# source.net
KiCad netlist of a schematic drawn in Altium Designer
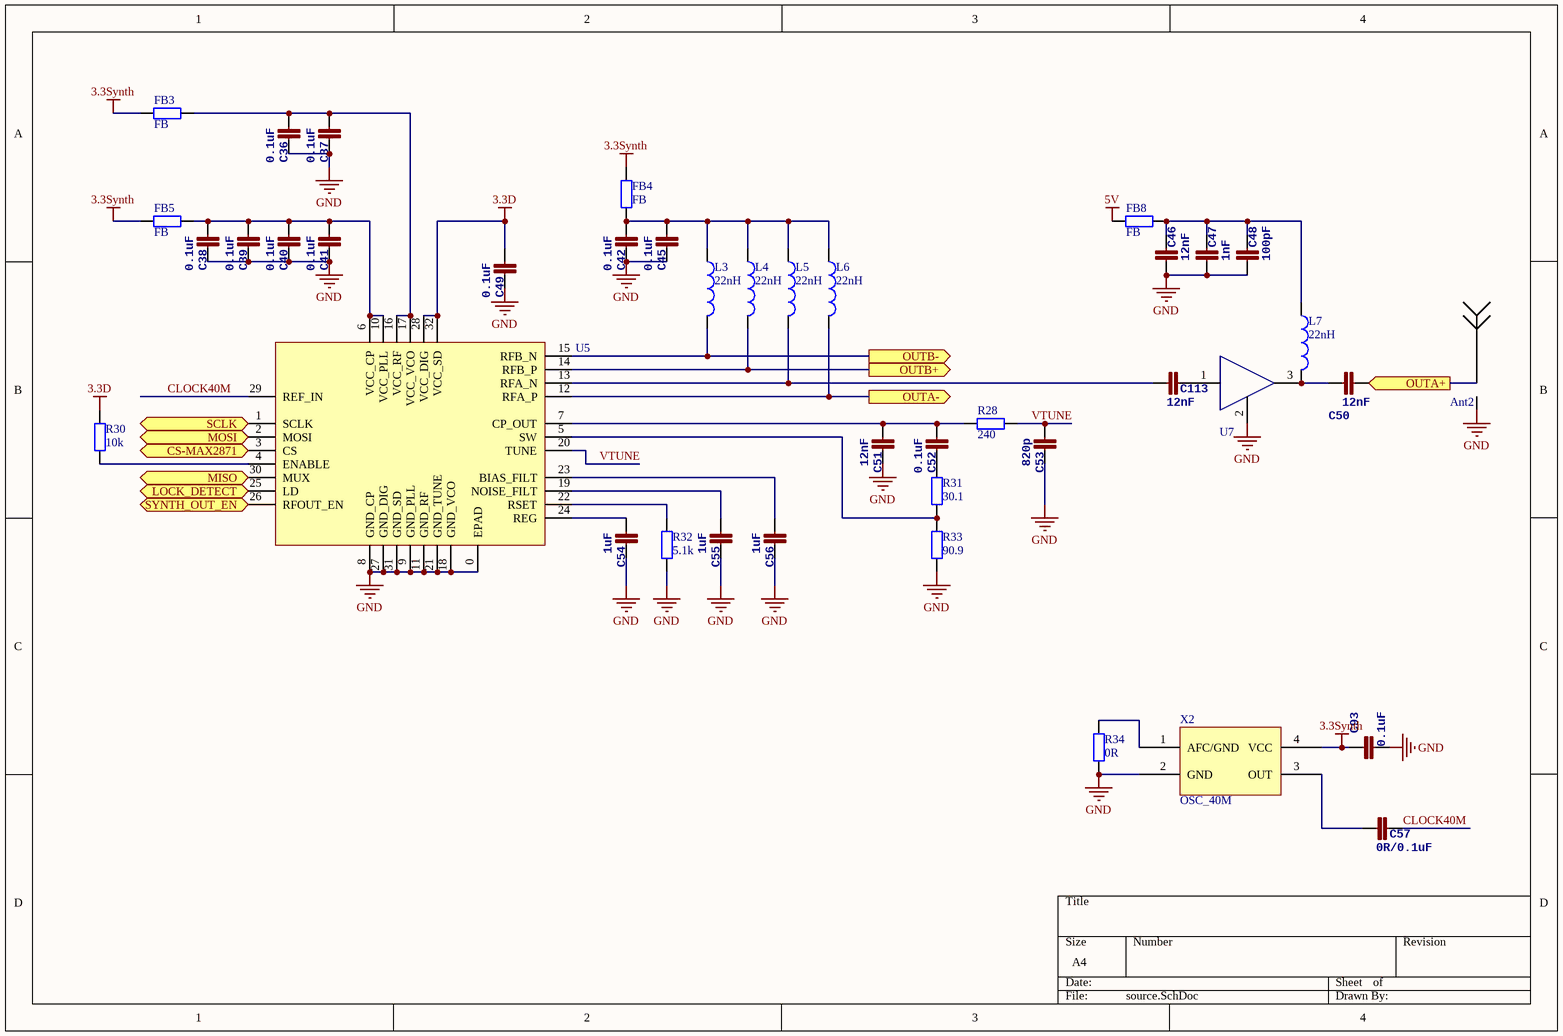
[diagram p0: source.SchDoc]

(export (version "E")
  (design (tool "Eeschema 10.0.6"))
  (components
    (comp (ref "Ant2") (value "Antenna") (footprint "SMA-2") (libsource (lib "F4SDR") (part "Antenna")))
    (comp (ref "C36")
      (value "0.1uF")
      (footprint "0402")
      (description "<b>Capacitor</b>\nStandard 0603 ceramic capacitor, and 0.1\" leaded capacitor.")
      (fields (field (name "PARTNO") "CC0402ZRY5V7BB104"))
      (libsource (lib "pixhawk2") (part "CAP0402-CAP"))
    )
    (comp (ref "C37")
      (value "0.1uF")
      (footprint "0402")
      (description "<b>Capacitor</b>\nStandard 0603 ceramic capacitor, and 0.1\" leaded capacitor.")
      (fields (field (name "PARTNO") "CC0402ZRY5V7BB104"))
      (libsource (lib "pixhawk2") (part "CAP0402-CAP"))
    )
    (comp (ref "C38")
      (value "0.1uF")
      (footprint "0402")
      (description "<b>Capacitor</b>\nStandard 0603 ceramic capacitor, and 0.1\" leaded capacitor.")
      (fields (field (name "PARTNO") "CC0402ZRY5V7BB104"))
      (libsource (lib "pixhawk2") (part "CAP0402-CAP"))
    )
    (comp (ref "C39")
      (value "0.1uF")
      (footprint "0402")
      (description "<b>Capacitor</b>\nStandard 0603 ceramic capacitor, and 0.1\" leaded capacitor.")
      (fields (field (name "PARTNO") "CC0402ZRY5V7BB104"))
      (libsource (lib "pixhawk2") (part "CAP0402-CAP"))
    )
    (comp (ref "C40")
      (value "0.1uF")
      (footprint "0402")
      (description "<b>Capacitor</b>\nStandard 0603 ceramic capacitor, and 0.1\" leaded capacitor.")
      (fields (field (name "PARTNO") "CC0402ZRY5V7BB104"))
      (libsource (lib "pixhawk2") (part "CAP0402-CAP"))
    )
    (comp (ref "C41")
      (value "0.1uF")
      (footprint "0402")
      (description "<b>Capacitor</b>\nStandard 0603 ceramic capacitor, and 0.1\" leaded capacitor.")
      (fields (field (name "PARTNO") "CC0402ZRY5V7BB104"))
      (libsource (lib "pixhawk2") (part "CAP0402-CAP"))
    )
    (comp (ref "C42")
      (value "0.1uF")
      (footprint "0402")
      (description "<b>Capacitor</b>\nStandard 0603 ceramic capacitor, and 0.1\" leaded capacitor.")
      (fields (field (name "PARTNO") "CC0402ZRY5V7BB104"))
      (libsource (lib "pixhawk2") (part "CAP0402-CAP"))
    )
    (comp (ref "C45")
      (value "0.1uF")
      (footprint "0402")
      (description "<b>Capacitor</b>\nStandard 0603 ceramic capacitor, and 0.1\" leaded capacitor.")
      (fields (field (name "PARTNO") "CC0402ZRY5V7BB104"))
      (libsource (lib "pixhawk2") (part "CAP0402-CAP"))
    )
    (comp (ref "C46")
      (value "12nF")
      (footprint "0805")
      (description "<b>Capacitor</b>\nStandard 0603 ceramic capacitor, and 0.1\" leaded capacitor.")
      (fields (field (name "PARTNO") "CC0402ZRY5V7BB104"))
      (libsource (lib "") (part "CAP0402-CAP_2"))
    )
    (comp (ref "C47")
      (value "1nF")
      (footprint "0402")
      (description "<b>Capacitor</b>\nStandard 0603 ceramic capacitor, and 0.1\" leaded capacitor.")
      (fields (field (name "PARTNO") "CC0402ZRY5V7BB104"))
      (libsource (lib "") (part "CAP0402-CAP_2"))
    )
    (comp (ref "C48")
      (value "100pF")
      (footprint "0402")
      (description "<b>Capacitor</b>\nStandard 0603 ceramic capacitor, and 0.1\" leaded capacitor.")
      (fields (field (name "PARTNO") "CC0402ZRY5V7BB104"))
      (libsource (lib "") (part "CAP0402-CAP_2"))
    )
    (comp (ref "C49")
      (value "0.1uF")
      (footprint "0402")
      (description "<b>Capacitor</b>\nStandard 0603 ceramic capacitor, and 0.1\" leaded capacitor.")
      (fields (field (name "PARTNO") "CC0402ZRY5V7BB104"))
      (libsource (lib "pixhawk2") (part "CAP0402-CAP"))
    )
    (comp (ref "C50")
      (value "12nF")
      (footprint "0402")
      (description "<b>Capacitor</b>\nStandard 0603 ceramic capacitor, and 0.1\" leaded capacitor.")
      (fields (field (name "PARTNO") "CC0402ZRY5V7BB104"))
      (libsource (lib "") (part "CAP0402-CAP_1"))
    )
    (comp (ref "C51")
      (value "12nF")
      (footprint "0402")
      (description "<b>Capacitor</b>\nStandard 0603 ceramic capacitor, and 0.1\" leaded capacitor.")
      (fields (field (name "PARTNO") "CC0402ZRY5V7BB104"))
      (libsource (lib "pixhawk2") (part "CAP0402-CAP"))
    )
    (comp (ref "C52")
      (value "0.1uF")
      (footprint "0402")
      (description "<b>Capacitor</b>\nStandard 0603 ceramic capacitor, and 0.1\" leaded capacitor.")
      (fields (field (name "PARTNO") "CC0402ZRY5V7BB104"))
      (libsource (lib "pixhawk2") (part "CAP0402-CAP"))
    )
    (comp (ref "C53")
      (value "820p")
      (footprint "0402")
      (description "<b>Capacitor</b>\nStandard 0603 ceramic capacitor, and 0.1\" leaded capacitor.")
      (fields (field (name "PARTNO") "CC0402ZRY5V7BB104"))
      (libsource (lib "pixhawk2") (part "CAP0402-CAP"))
    )
    (comp (ref "C54")
      (value "1uF")
      (footprint "0402")
      (description "<b>Capacitor</b>\nStandard 0603 ceramic capacitor, and 0.1\" leaded capacitor.")
      (fields (field (name "PARTNO") "CC0402ZRY5V7BB104"))
      (libsource (lib "pixhawk2") (part "CAP0402-CAP"))
    )
    (comp (ref "C55")
      (value "1uF")
      (footprint "0402")
      (description "<b>Capacitor</b>\nStandard 0603 ceramic capacitor, and 0.1\" leaded capacitor.")
      (fields (field (name "PARTNO") "CC0402ZRY5V7BB104"))
      (libsource (lib "pixhawk2") (part "CAP0402-CAP"))
    )
    (comp (ref "C56")
      (value "1uF")
      (footprint "0402")
      (description "<b>Capacitor</b>\nStandard 0603 ceramic capacitor, and 0.1\" leaded capacitor.")
      (fields (field (name "PARTNO") "CC0402ZRY5V7BB104"))
      (libsource (lib "pixhawk2") (part "CAP0402-CAP"))
    )
    (comp (ref "C57")
      (value "0R/0.1uF")
      (footprint "0402")
      (description "<b>Capacitor</b>\nStandard 0603 ceramic capacitor, and 0.1\" leaded capacitor.")
      (fields (field (name "PARTNO") "CC0402ZRY5V7BB104"))
      (libsource (lib "") (part "CAP0402-CAP_1"))
    )
    (comp (ref "C93")
      (value "0.1uF")
      (footprint "0402")
      (description "<b>Capacitor</b>\nStandard 0603 ceramic capacitor, and 0.1\" leaded capacitor.")
      (fields (field (name "PARTNO") "CC0402ZRY5V7BB104"))
      (libsource (lib "") (part "CAP0402-CAP_1"))
    )
    (comp (ref "C113")
      (value "12nF")
      (footprint "0402")
      (description "<b>Capacitor</b>\nStandard 0603 ceramic capacitor, and 0.1\" leaded capacitor.")
      (fields (field (name "PARTNO") "CC0402ZRY5V7BB104"))
      (libsource (lib "") (part "CAP0402-CAP_1"))
    )
    (comp (ref "FB3")
      (value "FB")
      (footprint "0603")
      (description "Resistor")
      (fields (field (name "PUBLISHER") "Altium Limited"))
      (libsource (lib "") (part "Res2_2"))
    )
    (comp (ref "FB4")
      (value "FB")
      (footprint "0603")
      (description "Resistor")
      (fields (field (name "PUBLISHER") "Altium Limited"))
      (libsource (lib "") (part "Res2_3"))
    )
    (comp (ref "FB5")
      (value "FB")
      (footprint "0603")
      (description "Resistor")
      (fields (field (name "PUBLISHER") "Altium Limited"))
      (libsource (lib "") (part "Res2_2"))
    )
    (comp (ref "FB8")
      (value "FB")
      (footprint "0603")
      (description "Resistor")
      (fields (field (name "PUBLISHER") "Altium Limited"))
      (libsource (lib "") (part "Res2_1"))
    )
    (comp (ref "L3")
      (value "22nH")
      (footprint "0402")
      (description "Inductor")
      (fields (field (name "PUBLISHER") "Altium Limited"))
      (libsource (lib "Miscellaneous Devices") (part "Inductor"))
    )
    (comp (ref "L4")
      (value "22nH")
      (footprint "0402")
      (description "Inductor")
      (fields (field (name "PUBLISHER") "Altium Limited"))
      (libsource (lib "Miscellaneous Devices") (part "Inductor"))
    )
    (comp (ref "L5")
      (value "22nH")
      (footprint "0402")
      (description "Inductor")
      (fields (field (name "PUBLISHER") "Altium Limited"))
      (libsource (lib "Miscellaneous Devices") (part "Inductor"))
    )
    (comp (ref "L6")
      (value "22nH")
      (footprint "0402")
      (description "Inductor")
      (fields (field (name "PUBLISHER") "Altium Limited"))
      (libsource (lib "Miscellaneous Devices") (part "Inductor"))
    )
    (comp (ref "L7")
      (value "22nH")
      (footprint "0603")
      (description "Inductor")
      (fields (field (name "PUBLISHER") "Altium Limited"))
      (libsource (lib "Miscellaneous Devices") (part "Inductor"))
    )
    (comp (ref "R28")
      (value "240")
      (footprint "0402")
      (description "Resistor")
      (fields (field (name "PUBLISHER") "Altium Limited"))
      (libsource (lib "") (part "Res2_2"))
    )
    (comp (ref "R30")
      (value "10k")
      (footprint "0402")
      (description "Resistor")
      (fields (field (name "PUBLISHER") "Altium Limited"))
      (libsource (lib "Miscellaneous Devices") (part "Res2"))
    )
    (comp (ref "R31")
      (value "30.1")
      (footprint "0402")
      (description "Resistor")
      (fields (field (name "PUBLISHER") "Altium Limited"))
      (libsource (lib "Miscellaneous Devices") (part "Res2"))
    )
    (comp (ref "R32")
      (value "5.1k")
      (footprint "0402")
      (description "Resistor")
      (fields (field (name "PUBLISHER") "Altium Limited"))
      (libsource (lib "Miscellaneous Devices") (part "Res2"))
    )
    (comp (ref "R33")
      (value "90.9")
      (footprint "0402")
      (description "Resistor")
      (fields (field (name "PUBLISHER") "Altium Limited"))
      (libsource (lib "Miscellaneous Devices") (part "Res2"))
    )
    (comp (ref "R34")
      (value "0R")
      (footprint "0402")
      (description "Resistor")
      (fields (field (name "PUBLISHER") "Altium Limited"))
      (libsource (lib "") (part "Res2_3"))
    )
    (comp (ref "U5") (value "MAX2871") (footprint "MAX2871") (libsource (lib "F4SDR") (part "MAX2871")))
    (comp (ref "U7") (value "AMP-SOT89") (footprint "SOT-89") (libsource (lib "F4SDR") (part "AMP-SOT89")))
    (comp (ref "X2") (value "OSC_40M") (footprint "TXC_7Q") (libsource (lib "F4SDR") (part "OSC_40M")))
  )
  (nets
    (net (code "1") (name "/CLOCK40M") (class "Default")
      (node (ref "C57") (pin "2") (pinfunction "2_2") (pintype "passive"))
      (node (ref "U5") (pin "29") (pinfunction "REF_IN_29") (pintype "passive"))
    )
    (net (code "2") (name "/CS-MAX2871") (class "Default")
      (node (ref "U5") (pin "3") (pinfunction "CS_3") (pintype "passive"))
    )
    (net (code "3") (name "/LOCK_DETECT") (class "Default")
      (node (ref "U5") (pin "25") (pinfunction "LD_25") (pintype "passive"))
    )
    (net (code "4") (name "/MISO") (class "Default")
      (node (ref "U5") (pin "30") (pinfunction "MUX_30") (pintype "passive"))
    )
    (net (code "5") (name "/MOSI") (class "Default")
      (node (ref "U5") (pin "2") (pinfunction "MOSI_2") (pintype "passive"))
    )
    (net (code "6") (name "/OUTA+") (class "Default")
      (node (ref "Ant2") (pin "1") (pinfunction "1_1") (pintype "passive"))
      (node (ref "C50") (pin "2") (pinfunction "2_2") (pintype "passive"))
    )
    (net (code "7") (name "/OUTA-") (class "Default")
      (node (ref "L6") (pin "2") (pinfunction "2_2") (pintype "passive"))
      (node (ref "U5") (pin "12") (pinfunction "RFA_P_12") (pintype "passive"))
    )
    (net (code "8") (name "/OUTB+") (class "Default")
      (node (ref "L4") (pin "2") (pinfunction "2_2") (pintype "passive"))
      (node (ref "U5") (pin "14") (pinfunction "RFB_P_14") (pintype "passive"))
    )
    (net (code "9") (name "/OUTB-") (class "Default")
      (node (ref "L3") (pin "2") (pinfunction "2_2") (pintype "passive"))
      (node (ref "U5") (pin "15") (pinfunction "RFB_N_15") (pintype "passive"))
    )
    (net (code "10") (name "/SCLK") (class "Default")
      (node (ref "U5") (pin "1") (pinfunction "SCLK_1") (pintype "passive"))
    )
    (net (code "11") (name "/SYNTH_OUT_EN") (class "Default")
      (node (ref "U5") (pin "26") (pinfunction "RFOUT_EN_26") (pintype "passive"))
    )
    (net (code "12") (name "/VTUNE") (class "Default")
      (node (ref "C53") (pin "1") (pinfunction "1_1") (pintype "passive"))
      (node (ref "R28") (pin "1") (pinfunction "1_1") (pintype "passive"))
      (node (ref "U5") (pin "20") (pinfunction "TUNE_20") (pintype "passive"))
    )
    (net (code "13") (name "3.3D") (class "Default")
      (node (ref "C49") (pin "1") (pinfunction "1_1") (pintype "passive"))
      (node (ref "R30") (pin "2") (pinfunction "2_2") (pintype "passive"))
      (node (ref "U5") (pin "28") (pinfunction "VCC_DIG_28") (pintype "passive"))
      (node (ref "U5") (pin "32") (pinfunction "VCC_SD_32") (pintype "passive"))
    )
    (net (code "14") (name "3.3Synth") (class "Default")
      (node (ref "C93") (pin "1") (pinfunction "1_1") (pintype "passive"))
      (node (ref "FB3") (pin "2") (pinfunction "2_2") (pintype "passive"))
      (node (ref "FB4") (pin "1") (pinfunction "1_1") (pintype "passive"))
      (node (ref "FB5") (pin "2") (pinfunction "2_2") (pintype "passive"))
      (node (ref "X2") (pin "4") (pinfunction "VCC_4") (pintype "passive"))
    )
    (net (code "15") (name "5V") (class "Default")
      (node (ref "FB8") (pin "1") (pinfunction "1_1") (pintype "passive"))
    )
    (net (code "16") (name "GND") (class "Default")
      (node (ref "Ant2") (pin "GND") (pinfunction "G_GND") (pintype "passive"))
      (node (ref "C36") (pin "2") (pinfunction "2_2") (pintype "passive"))
      (node (ref "C37") (pin "2") (pinfunction "2_2") (pintype "passive"))
      (node (ref "C38") (pin "2") (pinfunction "2_2") (pintype "passive"))
      (node (ref "C39") (pin "2") (pinfunction "2_2") (pintype "passive"))
      (node (ref "C40") (pin "2") (pinfunction "2_2") (pintype "passive"))
      (node (ref "C41") (pin "2") (pinfunction "2_2") (pintype "passive"))
      (node (ref "C42") (pin "2") (pinfunction "2_2") (pintype "passive"))
      (node (ref "C45") (pin "2") (pinfunction "2_2") (pintype "passive"))
      (node (ref "C46") (pin "1") (pinfunction "1_1") (pintype "passive"))
      (node (ref "C47") (pin "1") (pinfunction "1_1") (pintype "passive"))
      (node (ref "C48") (pin "1") (pinfunction "1_1") (pintype "passive"))
      (node (ref "C49") (pin "2") (pinfunction "2_2") (pintype "passive"))
      (node (ref "C51") (pin "2") (pinfunction "2_2") (pintype "passive"))
      (node (ref "C53") (pin "2") (pinfunction "2_2") (pintype "passive"))
      (node (ref "C54") (pin "2") (pinfunction "2_2") (pintype "passive"))
      (node (ref "C55") (pin "2") (pinfunction "2_2") (pintype "passive"))
      (node (ref "C56") (pin "2") (pinfunction "2_2") (pintype "passive"))
      (node (ref "C93") (pin "2") (pinfunction "2_2") (pintype "passive"))
      (node (ref "R32") (pin "1") (pinfunction "1_1") (pintype "passive"))
      (node (ref "R33") (pin "1") (pinfunction "1_1") (pintype "passive"))
      (node (ref "R34") (pin "2") (pinfunction "2_2") (pintype "passive"))
      (node (ref "U5") (pin "0") (pinfunction "EPAD_0") (pintype "passive"))
      (node (ref "U5") (pin "11") (pinfunction "GND_RF_11") (pintype "passive"))
      (node (ref "U5") (pin "18") (pinfunction "GND_VCO_18") (pintype "passive"))
      (node (ref "U5") (pin "21") (pinfunction "GND_TUNE_21") (pintype "passive"))
      (node (ref "U5") (pin "27") (pinfunction "GND_DIG_27") (pintype "passive"))
      (node (ref "U5") (pin "31") (pinfunction "GND_SD_31") (pintype "passive"))
      (node (ref "U5") (pin "8") (pinfunction "GND_CP_8") (pintype "passive"))
      (node (ref "U5") (pin "9") (pinfunction "GND_PLL_9") (pintype "passive"))
      (node (ref "U7") (pin "2") (pinfunction "2_2") (pintype "passive"))
      (node (ref "X2") (pin "2") (pinfunction "GND_2") (pintype "passive"))
    )
    (net (code "17") (name "Net-(C42-Pad1)") (class "Default")
      (node (ref "C42") (pin "1") (pinfunction "1_1") (pintype "passive"))
      (node (ref "C45") (pin "1") (pinfunction "1_1") (pintype "passive"))
      (node (ref "FB4") (pin "2") (pinfunction "2_2") (pintype "passive"))
      (node (ref "L3") (pin "1") (pinfunction "1_1") (pintype "passive"))
      (node (ref "L4") (pin "1") (pinfunction "1_1") (pintype "passive"))
      (node (ref "L5") (pin "1") (pinfunction "1_1") (pintype "passive"))
      (node (ref "L6") (pin "1") (pinfunction "1_1") (pintype "passive"))
    )
    (net (code "18") (name "Net-(C46-Pad2)") (class "Default")
      (node (ref "C46") (pin "2") (pinfunction "2_2") (pintype "passive"))
      (node (ref "C47") (pin "2") (pinfunction "2_2") (pintype "passive"))
      (node (ref "C48") (pin "2") (pinfunction "2_2") (pintype "passive"))
      (node (ref "FB8") (pin "2") (pinfunction "2_2") (pintype "passive"))
      (node (ref "L7") (pin "1") (pinfunction "1_1") (pintype "passive"))
    )
    (net (code "19") (name "Net-(C50-Pad1)") (class "Default")
      (node (ref "C50") (pin "1") (pinfunction "1_1") (pintype "passive"))
      (node (ref "L7") (pin "2") (pinfunction "2_2") (pintype "passive"))
      (node (ref "U7") (pin "3") (pinfunction "3_3") (pintype "passive"))
    )
    (net (code "20") (name "Net-(C52-Pad2)") (class "Default")
      (node (ref "C52") (pin "2") (pinfunction "2_2") (pintype "passive"))
      (node (ref "R31") (pin "2") (pinfunction "2_2") (pintype "passive"))
    )
    (net (code "21") (name "Net-(C113-Pad2)") (class "Default")
      (node (ref "C113") (pin "2") (pinfunction "2_2") (pintype "passive"))
      (node (ref "U7") (pin "1") (pinfunction "1_1") (pintype "passive"))
    )
    (net (code "22") (name "Net-(U5-BIAS_FILT)") (class "Default")
      (node (ref "C56") (pin "1") (pinfunction "1_1") (pintype "passive"))
      (node (ref "U5") (pin "23") (pinfunction "BIAS_FILT_23") (pintype "passive"))
    )
    (net (code "23") (name "Net-(U5-CP_OUT)") (class "Default")
      (node (ref "C51") (pin "1") (pinfunction "1_1") (pintype "passive"))
      (node (ref "C52") (pin "1") (pinfunction "1_1") (pintype "passive"))
      (node (ref "R28") (pin "2") (pinfunction "2_2") (pintype "passive"))
      (node (ref "U5") (pin "7") (pinfunction "CP_OUT_7") (pintype "passive"))
    )
    (net (code "24") (name "Net-(U5-ENABLE)") (class "Default")
      (node (ref "R30") (pin "1") (pinfunction "1_1") (pintype "passive"))
      (node (ref "U5") (pin "4") (pinfunction "ENABLE_4") (pintype "passive"))
    )
    (net (code "25") (name "Net-(U5-NOISE_FILT)") (class "Default")
      (node (ref "C55") (pin "1") (pinfunction "1_1") (pintype "passive"))
      (node (ref "U5") (pin "19") (pinfunction "NOISE_FILT_19") (pintype "passive"))
    )
    (net (code "26") (name "Net-(U5-REG)") (class "Default")
      (node (ref "C54") (pin "1") (pinfunction "1_1") (pintype "passive"))
      (node (ref "U5") (pin "24") (pinfunction "REG_24") (pintype "passive"))
    )
    (net (code "27") (name "Net-(U5-RFA_N)") (class "Default")
      (node (ref "C113") (pin "1") (pinfunction "1_1") (pintype "passive"))
      (node (ref "L5") (pin "2") (pinfunction "2_2") (pintype "passive"))
      (node (ref "U5") (pin "13") (pinfunction "RFA_N_13") (pintype "passive"))
    )
    (net (code "28") (name "Net-(U5-RSET)") (class "Default")
      (node (ref "R32") (pin "2") (pinfunction "2_2") (pintype "passive"))
      (node (ref "U5") (pin "22") (pinfunction "RSET_22") (pintype "passive"))
    )
    (net (code "29") (name "Net-(U5-SW)") (class "Default")
      (node (ref "R31") (pin "1") (pinfunction "1_1") (pintype "passive"))
      (node (ref "R33") (pin "2") (pinfunction "2_2") (pintype "passive"))
      (node (ref "U5") (pin "5") (pinfunction "SW_5") (pintype "passive"))
    )
    (net (code "30") (name "Net-(U5-VCC_CP)") (class "Default")
      (node (ref "C38") (pin "1") (pinfunction "1_1") (pintype "passive"))
      (node (ref "C39") (pin "1") (pinfunction "1_1") (pintype "passive"))
      (node (ref "C40") (pin "1") (pinfunction "1_1") (pintype "passive"))
      (node (ref "C41") (pin "1") (pinfunction "1_1") (pintype "passive"))
      (node (ref "FB5") (pin "1") (pinfunction "1_1") (pintype "passive"))
      (node (ref "U5") (pin "10") (pinfunction "VCC_PLL_10") (pintype "passive"))
      (node (ref "U5") (pin "6") (pinfunction "VCC_CP_6") (pintype "passive"))
    )
    (net (code "31") (name "Net-(U5-VCC_RF)") (class "Default")
      (node (ref "C36") (pin "1") (pinfunction "1_1") (pintype "passive"))
      (node (ref "C37") (pin "1") (pinfunction "1_1") (pintype "passive"))
      (node (ref "FB3") (pin "1") (pinfunction "1_1") (pintype "passive"))
      (node (ref "U5") (pin "16") (pinfunction "VCC_RF_16") (pintype "passive"))
      (node (ref "U5") (pin "17") (pinfunction "VCC_VCO_17") (pintype "passive"))
    )
    (net (code "32") (name "Net-(X2-AFC{slash}GND)") (class "Default")
      (node (ref "R34") (pin "1") (pinfunction "1_1") (pintype "passive"))
      (node (ref "X2") (pin "1") (pinfunction "AFC/GND_1") (pintype "passive"))
    )
    (net (code "33") (name "Net-(X2-OUT)") (class "Default")
      (node (ref "C57") (pin "1") (pinfunction "1_1") (pintype "passive"))
      (node (ref "X2") (pin "3") (pinfunction "OUT_3") (pintype "passive"))
    )
  )
)
